# schematic.net
KiCad netlist of a schematic drawn in EAGLE
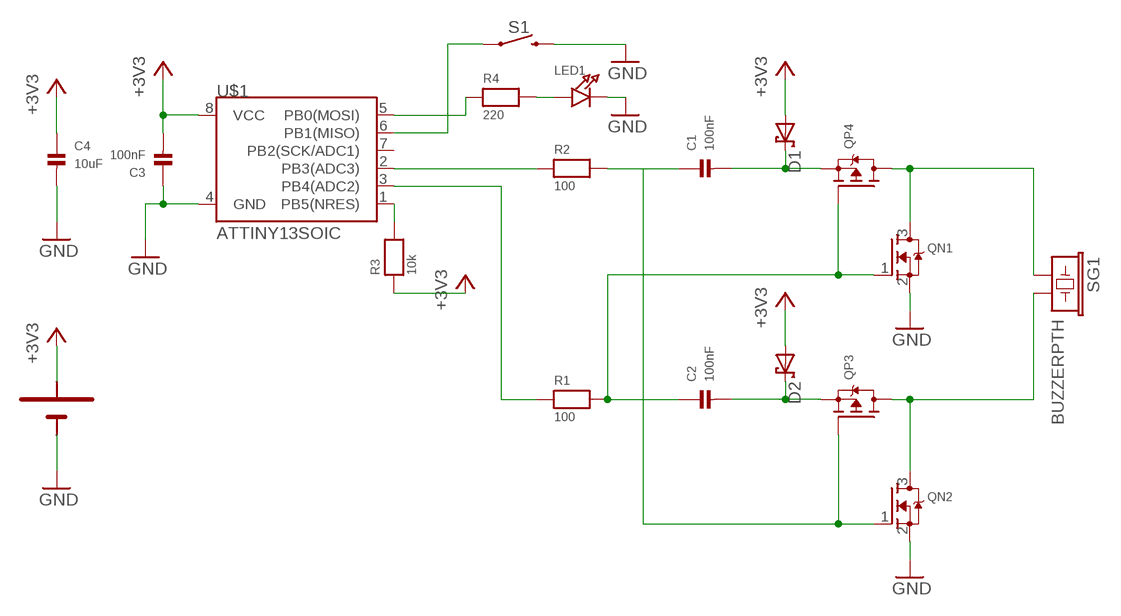
[diagram p0: schematic, sheet 1]

(export (version "E")
  (design (tool "Eeschema 10.0.6"))
  (components
    (comp (ref "C1")
      (value "100nF")
      (footprint "eagle-import:0805")
      (libsource (lib "eagle-import") (part "CAP_CERAMIC0805"))
    )
    (comp (ref "C2")
      (value "100nF")
      (footprint "eagle-import:0805")
      (libsource (lib "eagle-import") (part "CAP_CERAMIC0805"))
    )
    (comp (ref "C3")
      (value "100nF")
      (footprint "eagle-import:0805")
      (libsource (lib "eagle-import") (part "CAP_CERAMIC0805"))
    )
    (comp (ref "C4")
      (value "10uF")
      (footprint "eagle-import:0805")
      (libsource (lib "eagle-import") (part "CAP_CERAMIC0805"))
    )
    (comp (ref "D1")
      (value "SCOTTKY")
      (footprint "eagle-import:SOD123F")
      (libsource (lib "eagle-import") (part "BAS40H"))
    )
    (comp (ref "D2")
      (value "BAT20J")
      (footprint "eagle-import:SOD123F")
      (libsource (lib "eagle-import") (part "BAS40H"))
    )
    (comp (ref "LED1")
      (value "LED0805_NOOUTLINE")
      (footprint "eagle-import:CHIPLED_0805_NOOUTLINE")
      (libsource (lib "eagle-import") (part "LED0805_NOOUTLINE"))
    )
    (comp (ref "QN1")
      (value "MOSFET-NWIDE")
      (footprint "eagle-import:SOT23-WIDE")
      (libsource (lib "eagle-import") (part "MOSFET-NWIDE"))
    )
    (comp (ref "QN2")
      (value "MOSFET-NWIDE")
      (footprint "eagle-import:SOT23-WIDE")
      (libsource (lib "eagle-import") (part "MOSFET-NWIDE"))
    )
    (comp (ref "QP3")
      (value "MOSFET-PWIDE")
      (footprint "eagle-import:SOT23-WIDE")
      (libsource (lib "eagle-import") (part "MOSFET-PWIDE"))
    )
    (comp (ref "QP4")
      (value "MOSFET-PWIDE")
      (footprint "eagle-import:SOT23-WIDE")
      (libsource (lib "eagle-import") (part "MOSFET-PWIDE"))
    )
    (comp (ref "R1")
      (value "100")
      (footprint "eagle-import:0805")
      (libsource (lib "eagle-import") (part "RESISTOR0805"))
    )
    (comp (ref "R2")
      (value "100")
      (footprint "eagle-import:0805")
      (libsource (lib "eagle-import") (part "RESISTOR0805"))
    )
    (comp (ref "R3")
      (value "10k")
      (footprint "eagle-import:0805")
      (libsource (lib "eagle-import") (part "RESISTOR0805"))
    )
    (comp (ref "R4")
      (value "220")
      (footprint "eagle-import:0805")
      (libsource (lib "eagle-import") (part "RESISTOR0805"))
    )
    (comp (ref "S1")
      (value "MOMENTARY-SWITCH-SPST-SMD-5.2MM")
      (footprint "eagle-import:TACTILE_SWITCH_SMD_5.2MM")
      (libsource (lib "eagle-import") (part "MOMENTARY-SWITCH-SPST-SMD-5.2MM"))
    )
    (comp (ref "SG1")
      (value "BUZZERPTH")
      (footprint "eagle-import:BUZZER-12MM")
      (libsource (lib "eagle-import") (part "BUZZERPTH"))
    )
    (comp (ref "U$1")
      (value "ATTINY13SOIC")
      (footprint "eagle-import:SO08")
      (libsource (lib "eagle-import") (part "ATTINY13SOIC"))
    )
    (comp (ref "U$2")
      (value "CR2032")
      (footprint "eagle-import:COIN")
      (libsource (lib "eagle-import") (part "2032"))
    )
  )
  (nets
    (net (code "1") (name "+3V3") (class "Default")
      (node (ref "C3") (pin "2") (pinfunction "P$2_2") (pintype "passive"))
      (node (ref "C4") (pin "1") (pinfunction "P$1_1") (pintype "passive"))
      (node (ref "D1") (pin "2") (pinfunction "A_2") (pintype "passive"))
      (node (ref "D2") (pin "2") (pinfunction "A_2") (pintype "passive"))
      (node (ref "R3") (pin "1") (pinfunction "1_1") (pintype "passive"))
      (node (ref "U$1") (pin "8") (pinfunction "VCC_8") (pintype "bidirectional"))
      (node (ref "U$2") (pin "+") (pinfunction "+_+") (pintype "passive"))
    )
    (net (code "2") (name "GND") (class "Default")
      (node (ref "C3") (pin "1") (pinfunction "P$1_1") (pintype "passive"))
      (node (ref "C4") (pin "2") (pinfunction "P$2_2") (pintype "passive"))
      (node (ref "LED1") (pin "C") (pinfunction "C_C") (pintype "passive"))
      (node (ref "QN1") (pin "2") (pinfunction "S_2") (pintype "bidirectional"))
      (node (ref "QN2") (pin "2") (pinfunction "S_2") (pintype "bidirectional"))
      (node (ref "S1") (pin "3") (pinfunction "2_3") (pintype "passive"))
      (node (ref "U$1") (pin "4") (pinfunction "GND_4") (pintype "bidirectional"))
      (node (ref "U$2") (pin "-") (pinfunction "-_-") (pintype "passive"))
    )
    (net (code "3") (name "Net-(C1-P$1)") (class "Default")
      (node (ref "C1") (pin "1") (pinfunction "P$1_1") (pintype "passive"))
      (node (ref "QN2") (pin "1") (pinfunction "G_1") (pintype "bidirectional"))
      (node (ref "QP3") (pin "1") (pinfunction "G_1") (pintype "passive"))
      (node (ref "R2") (pin "2") (pinfunction "2_2") (pintype "passive"))
    )
    (net (code "4") (name "Net-(C1-P$2)") (class "Default")
      (node (ref "C1") (pin "2") (pinfunction "P$2_2") (pintype "passive"))
      (node (ref "D1") (pin "1") (pinfunction "K_1") (pintype "passive"))
      (node (ref "QP4") (pin "2") (pinfunction "S_2") (pintype "passive"))
    )
    (net (code "5") (name "Net-(C2-P$1)") (class "Default")
      (node (ref "C2") (pin "1") (pinfunction "P$1_1") (pintype "passive"))
      (node (ref "QN1") (pin "1") (pinfunction "G_1") (pintype "bidirectional"))
      (node (ref "QP4") (pin "1") (pinfunction "G_1") (pintype "passive"))
      (node (ref "R1") (pin "2") (pinfunction "2_2") (pintype "passive"))
    )
    (net (code "6") (name "Net-(C2-P$2)") (class "Default")
      (node (ref "C2") (pin "2") (pinfunction "P$2_2") (pintype "passive"))
      (node (ref "D2") (pin "1") (pinfunction "K_1") (pintype "passive"))
      (node (ref "QP3") (pin "2") (pinfunction "S_2") (pintype "passive"))
    )
    (net (code "7") (name "Net-(LED1-PadA)") (class "Default")
      (node (ref "LED1") (pin "A") (pinfunction "A_A") (pintype "passive"))
      (node (ref "R4") (pin "2") (pinfunction "2_2") (pintype "passive"))
    )
    (net (code "8") (name "Net-(QN1-D)") (class "Default")
      (node (ref "QN1") (pin "3") (pinfunction "D_3") (pintype "bidirectional"))
      (node (ref "QP4") (pin "3") (pinfunction "D_3") (pintype "passive"))
      (node (ref "SG1") (pin "+") (pinfunction "1_+") (pintype "passive"))
    )
    (net (code "9") (name "Net-(QN2-D)") (class "Default")
      (node (ref "QN2") (pin "3") (pinfunction "D_3") (pintype "bidirectional"))
      (node (ref "QP3") (pin "3") (pinfunction "D_3") (pintype "passive"))
      (node (ref "SG1") (pin "-") (pinfunction "2_-") (pintype "passive"))
    )
    (net (code "10") (name "Net-(U$1-PB0(MOSI))") (class "Default")
      (node (ref "R4") (pin "1") (pinfunction "1_1") (pintype "passive"))
      (node (ref "U$1") (pin "5") (pinfunction "PB0(MOSI)_5") (pintype "bidirectional"))
    )
    (net (code "11") (name "Net-(U$1-PB1(MISO))") (class "Default")
      (node (ref "S1") (pin "1") (pinfunction "1_1") (pintype "passive"))
      (node (ref "U$1") (pin "6") (pinfunction "PB1(MISO)_6") (pintype "bidirectional"))
    )
    (net (code "12") (name "Net-(U$1-PB3(ADC3))") (class "Default")
      (node (ref "R2") (pin "1") (pinfunction "1_1") (pintype "passive"))
      (node (ref "U$1") (pin "2") (pinfunction "PB3(ADC3)_2") (pintype "bidirectional"))
    )
    (net (code "13") (name "Net-(U$1-PB4(ADC2))") (class "Default")
      (node (ref "R1") (pin "1") (pinfunction "1_1") (pintype "passive"))
      (node (ref "U$1") (pin "3") (pinfunction "PB4(ADC2)_3") (pintype "bidirectional"))
    )
    (net (code "14") (name "Net-(U$1-PB5(NRES))") (class "Default")
      (node (ref "R3") (pin "2") (pinfunction "2_2") (pintype "passive"))
      (node (ref "U$1") (pin "1") (pinfunction "PB5(NRES)_1") (pintype "bidirectional"))
    )
    (net (code "15") (name "unconnected-(U$1-PB2(SCK{slash}ADC1)-Pad7)") (class "Default")
      (node (ref "U$1") (pin "7") (pinfunction "PB2(SCK/ADC1)_7") (pintype "bidirectional"))
    )
  )
)
